# hello328p-v1.net
KiCad netlist of a schematic drawn in EAGLE
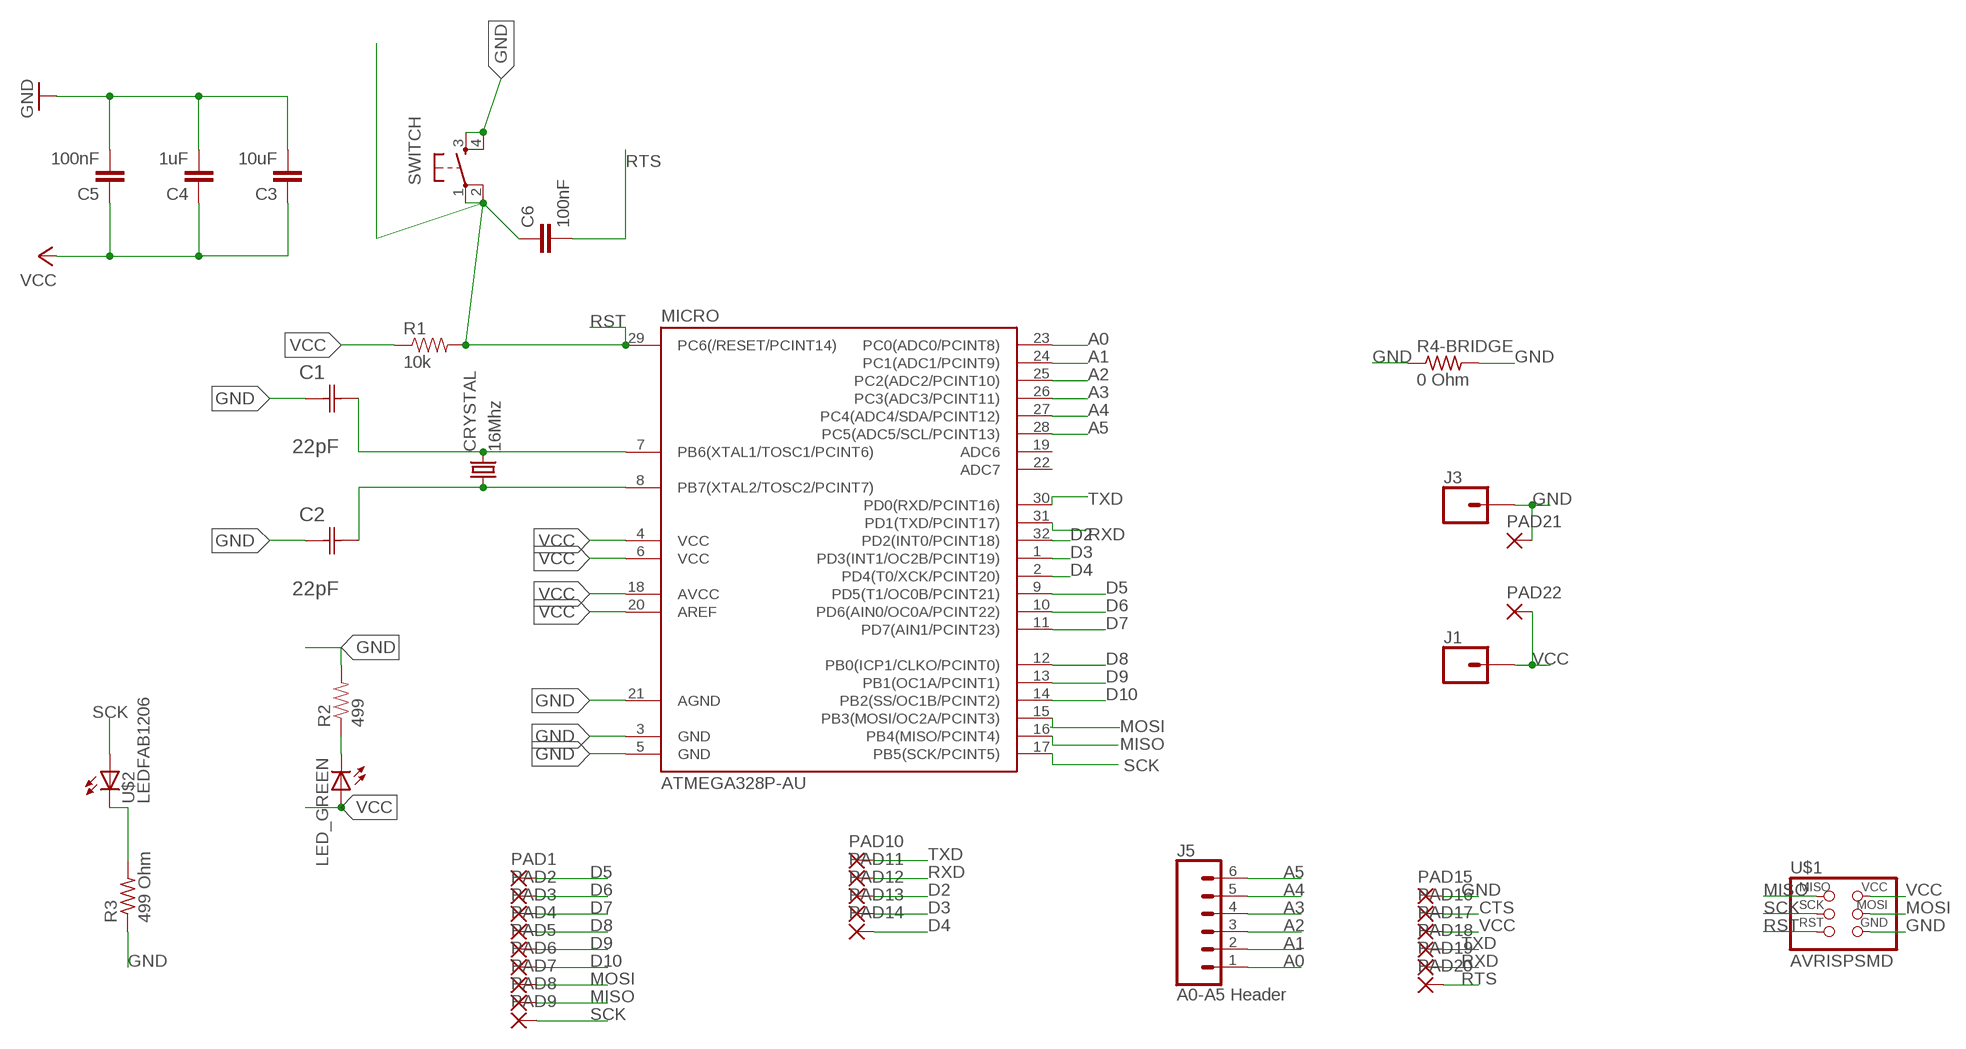
[diagram p0: schematic, sheet 1]

(export (version "E")
  (design (tool "Eeschema 10.0.6"))
  (components
    (comp (ref "C1")
      (value "22pF")
      (footprint "eagle-import:CAPC3216X178N")
      (fields (field (name "MPN") "0612ZC225MAT2A") (field (name "TOLERANCE") "±20%"))
      (libsource (lib "eagle-import") (part "0612ZC225MAT2A"))
    )
    (comp (ref "C2")
      (value "22pF")
      (footprint "eagle-import:CAPC3216X178N")
      (fields (field (name "MPN") "0612ZC225MAT2A") (field (name "TOLERANCE") "±20%"))
      (libsource (lib "eagle-import") (part "0612ZC225MAT2A"))
    )
    (comp (ref "C3")
      (value "10uF")
      (footprint "eagle-import:1206")
      (libsource (lib "eagle-import") (part "CAP1206"))
    )
    (comp (ref "C4")
      (value "1uF")
      (footprint "eagle-import:1206")
      (libsource (lib "eagle-import") (part "CAP1206"))
    )
    (comp (ref "C5")
      (value "100nF")
      (footprint "eagle-import:1206")
      (libsource (lib "eagle-import") (part "CAP1206"))
    )
    (comp (ref "C6")
      (value "100nF")
      (footprint "eagle-import:1206")
      (libsource (lib "eagle-import") (part "CAP1206"))
    )
    (comp (ref "CRYSTAL")
      (value "16Mhz")
      (footprint "eagle-import:CSM-7X-DU")
      (libsource (lib "eagle-import") (part "CSM-7X-DU"))
    )
    (comp (ref "J1")
      (value "CONN_01SNAP-MALE")
      (footprint "eagle-import:SNAP-MALE")
      (libsource (lib "eagle-import") (part "CONN_01SNAP-MALE"))
    )
    (comp (ref "J3")
      (value "CONN_01SNAP-MALE")
      (footprint "eagle-import:SNAP-MALE")
      (libsource (lib "eagle-import") (part "CONN_01SNAP-MALE"))
    )
    (comp (ref "J5")
      (value "A0-A5 Header")
      (footprint "eagle-import:1X06_SMD_MALE")
      (libsource (lib "eagle-import") (part "CONN_06SMD_MALE"))
    )
    (comp (ref "LED_GREEN")
      (value "LED1206")
      (footprint "eagle-import:1206")
      (libsource (lib "eagle-import") (part "LED1206"))
    )
    (comp (ref "MICRO")
      (value "ATMEGA328P-AU")
      (footprint "eagle-import:TQFP32-08")
      (libsource (lib "eagle-import") (part "ATMEGA48/88/168-AU"))
    )
    (comp (ref "PAD1")
      (value "SMD2")
      (footprint "eagle-import:SMD1,27-2,54")
      (libsource (lib "eagle-import") (part "SMD2"))
    )
    (comp (ref "PAD2")
      (value "SMD2")
      (footprint "eagle-import:SMD1,27-2,54")
      (libsource (lib "eagle-import") (part "SMD2"))
    )
    (comp (ref "PAD3")
      (value "SMD2")
      (footprint "eagle-import:SMD1,27-2,54")
      (libsource (lib "eagle-import") (part "SMD2"))
    )
    (comp (ref "PAD4")
      (value "SMD2")
      (footprint "eagle-import:SMD1,27-2,54")
      (libsource (lib "eagle-import") (part "SMD2"))
    )
    (comp (ref "PAD5")
      (value "SMD2")
      (footprint "eagle-import:SMD1,27-2,54")
      (libsource (lib "eagle-import") (part "SMD2"))
    )
    (comp (ref "PAD6")
      (value "SMD2")
      (footprint "eagle-import:SMD1,27-2,54")
      (libsource (lib "eagle-import") (part "SMD2"))
    )
    (comp (ref "PAD7")
      (value "SMD2")
      (footprint "eagle-import:SMD1,27-2,54")
      (libsource (lib "eagle-import") (part "SMD2"))
    )
    (comp (ref "PAD8")
      (value "SMD2")
      (footprint "eagle-import:SMD1,27-2,54")
      (libsource (lib "eagle-import") (part "SMD2"))
    )
    (comp (ref "PAD9")
      (value "SMD2")
      (footprint "eagle-import:SMD1,27-2,54")
      (libsource (lib "eagle-import") (part "SMD2"))
    )
    (comp (ref "PAD10")
      (value "SMD2")
      (footprint "eagle-import:SMD1,27-2,54")
      (libsource (lib "eagle-import") (part "SMD2"))
    )
    (comp (ref "PAD11")
      (value "SMD2")
      (footprint "eagle-import:SMD1,27-2,54")
      (libsource (lib "eagle-import") (part "SMD2"))
    )
    (comp (ref "PAD12")
      (value "SMD2")
      (footprint "eagle-import:SMD1,27-2,54")
      (libsource (lib "eagle-import") (part "SMD2"))
    )
    (comp (ref "PAD13")
      (value "SMD2")
      (footprint "eagle-import:SMD1,27-2,54")
      (libsource (lib "eagle-import") (part "SMD2"))
    )
    (comp (ref "PAD14")
      (value "SMD2")
      (footprint "eagle-import:SMD1,27-2,54")
      (libsource (lib "eagle-import") (part "SMD2"))
    )
    (comp (ref "PAD15")
      (value "SMD2")
      (footprint "eagle-import:SMD1,27-2,54")
      (libsource (lib "eagle-import") (part "SMD2"))
    )
    (comp (ref "PAD16")
      (value "SMD2")
      (footprint "eagle-import:SMD1,27-2,54")
      (libsource (lib "eagle-import") (part "SMD2"))
    )
    (comp (ref "PAD17")
      (value "SMD2")
      (footprint "eagle-import:SMD1,27-2,54")
      (libsource (lib "eagle-import") (part "SMD2"))
    )
    (comp (ref "PAD18")
      (value "SMD2")
      (footprint "eagle-import:SMD1,27-2,54")
      (libsource (lib "eagle-import") (part "SMD2"))
    )
    (comp (ref "PAD19")
      (value "SMD2")
      (footprint "eagle-import:SMD1,27-2,54")
      (libsource (lib "eagle-import") (part "SMD2"))
    )
    (comp (ref "PAD20")
      (value "SMD2")
      (footprint "eagle-import:SMD1,27-2,54")
      (libsource (lib "eagle-import") (part "SMD2"))
    )
    (comp (ref "PAD21")
      (value "SMD2")
      (footprint "eagle-import:SMD1,27-2,54")
      (libsource (lib "eagle-import") (part "SMD2"))
    )
    (comp (ref "PAD22")
      (value "SMD2")
      (footprint "eagle-import:SMD1,27-2,54")
      (libsource (lib "eagle-import") (part "SMD2"))
    )
    (comp (ref "R1")
      (value "10k")
      (footprint "eagle-import:1206")
      (libsource (lib "eagle-import") (part "RESISTOR1206"))
    )
    (comp (ref "R2")
      (value "499")
      (footprint "eagle-import:1206")
      (libsource (lib "eagle-import") (part "RESISTOR1206"))
    )
    (comp (ref "R3")
      (value "499 Ohm")
      (footprint "eagle-import:R1206FAB")
      (libsource (lib "eagle-import") (part "RES-US1206FAB"))
    )
    (comp (ref "R4-BRIDGE")
      (value "0 Ohm")
      (footprint "eagle-import:R1206FAB")
      (libsource (lib "eagle-import") (part "RES-US1206FAB"))
    )
    (comp (ref "SWITCH")
      (value "6MM_SWITCH6MM_SWITCH")
      (footprint "eagle-import:6MM_SWITCH")
      (libsource (lib "eagle-import") (part "6MM_SWITCH6MM_SWITCH"))
    )
    (comp (ref "U$1")
      (value "AVRISPSMD")
      (footprint "eagle-import:2X03SMD")
      (libsource (lib "eagle-import") (part "AVRISPSMD"))
    )
    (comp (ref "U$2")
      (value "LEDFAB1206")
      (footprint "eagle-import:LED1206FAB")
      (libsource (lib "eagle-import") (part "LEDFAB1206"))
    )
  )
  (nets
    (net (code "1") (name "/A0") (class "Default")
      (node (ref "J5") (pin "1") (pinfunction "1_1") (pintype "passive"))
      (node (ref "MICRO") (pin "23") (pinfunction "PC0(ADC0/PCINT8)_23") (pintype "bidirectional"))
    )
    (net (code "2") (name "/A1") (class "Default")
      (node (ref "J5") (pin "2") (pinfunction "2_2") (pintype "passive"))
      (node (ref "MICRO") (pin "24") (pinfunction "PC1(ADC1/PCINT9)_24") (pintype "bidirectional"))
    )
    (net (code "3") (name "/A2") (class "Default")
      (node (ref "J5") (pin "3") (pinfunction "3_3") (pintype "passive"))
      (node (ref "MICRO") (pin "25") (pinfunction "PC2(ADC2/PCINT10)_25") (pintype "bidirectional"))
    )
    (net (code "4") (name "/A3") (class "Default")
      (node (ref "J5") (pin "4") (pinfunction "4_4") (pintype "passive"))
      (node (ref "MICRO") (pin "26") (pinfunction "PC3(ADC3/PCINT11)_26") (pintype "bidirectional"))
    )
    (net (code "5") (name "/A4") (class "Default")
      (node (ref "J5") (pin "5") (pinfunction "5_5") (pintype "passive"))
      (node (ref "MICRO") (pin "27") (pinfunction "PC4(ADC4/SDA/PCINT12)_27") (pintype "bidirectional"))
    )
    (net (code "6") (name "/A5") (class "Default")
      (node (ref "J5") (pin "6") (pinfunction "6_6") (pintype "passive"))
      (node (ref "MICRO") (pin "28") (pinfunction "PC5(ADC5/SCL/PCINT13)_28") (pintype "bidirectional"))
    )
    (net (code "7") (name "/CTS") (class "Default")
      (node (ref "PAD16") (pin "1") (pinfunction "P_1") (pintype "passive"))
    )
    (net (code "8") (name "/D2") (class "Default")
      (node (ref "MICRO") (pin "32") (pinfunction "PD2(INT0/PCINT18)_32") (pintype "bidirectional"))
      (node (ref "PAD12") (pin "1") (pinfunction "P_1") (pintype "passive"))
    )
    (net (code "9") (name "/D3") (class "Default")
      (node (ref "MICRO") (pin "1") (pinfunction "PD3(INT1/OC2B/PCINT19)_1") (pintype "bidirectional"))
      (node (ref "PAD13") (pin "1") (pinfunction "P_1") (pintype "passive"))
    )
    (net (code "10") (name "/D4") (class "Default")
      (node (ref "MICRO") (pin "2") (pinfunction "PD4(T0/XCK/PCINT20)_2") (pintype "bidirectional"))
      (node (ref "PAD14") (pin "1") (pinfunction "P_1") (pintype "passive"))
    )
    (net (code "11") (name "/D5") (class "Default")
      (node (ref "MICRO") (pin "9") (pinfunction "PD5(T1/OC0B/PCINT21)_9") (pintype "bidirectional"))
      (node (ref "PAD1") (pin "1") (pinfunction "P_1") (pintype "passive"))
    )
    (net (code "12") (name "/D6") (class "Default")
      (node (ref "MICRO") (pin "10") (pinfunction "PD6(AIN0/OC0A/PCINT22)_10") (pintype "bidirectional"))
      (node (ref "PAD2") (pin "1") (pinfunction "P_1") (pintype "passive"))
    )
    (net (code "13") (name "/D7") (class "Default")
      (node (ref "MICRO") (pin "11") (pinfunction "PD7(AIN1/PCINT23)_11") (pintype "bidirectional"))
      (node (ref "PAD3") (pin "1") (pinfunction "P_1") (pintype "passive"))
    )
    (net (code "14") (name "/D8") (class "Default")
      (node (ref "MICRO") (pin "12") (pinfunction "PB0(ICP1/CLKO/PCINT0)_12") (pintype "bidirectional"))
      (node (ref "PAD4") (pin "1") (pinfunction "P_1") (pintype "passive"))
    )
    (net (code "15") (name "/D9") (class "Default")
      (node (ref "MICRO") (pin "13") (pinfunction "PB1(OC1A/PCINT1)_13") (pintype "bidirectional"))
      (node (ref "PAD5") (pin "1") (pinfunction "P_1") (pintype "passive"))
    )
    (net (code "16") (name "/D10") (class "Default")
      (node (ref "MICRO") (pin "14") (pinfunction "PB2(SS/OC1B/PCINT2)_14") (pintype "bidirectional"))
      (node (ref "PAD6") (pin "1") (pinfunction "P_1") (pintype "passive"))
    )
    (net (code "17") (name "/MISO") (class "Default")
      (node (ref "MICRO") (pin "16") (pinfunction "PB4(MISO/PCINT4)_16") (pintype "bidirectional"))
      (node (ref "PAD8") (pin "1") (pinfunction "P_1") (pintype "passive"))
      (node (ref "U$1") (pin "1") (pinfunction "MISO_1") (pintype "passive"))
    )
    (net (code "18") (name "/MOSI") (class "Default")
      (node (ref "MICRO") (pin "15") (pinfunction "PB3(MOSI/OC2A/PCINT3)_15") (pintype "bidirectional"))
      (node (ref "PAD7") (pin "1") (pinfunction "P_1") (pintype "passive"))
      (node (ref "U$1") (pin "4") (pinfunction "MOSI_4") (pintype "passive"))
    )
    (net (code "19") (name "/RST") (class "Default")
      (node (ref "C6") (pin "1") (pinfunction "1_1") (pintype "passive"))
      (node (ref "MICRO") (pin "29") (pinfunction "PC6(/RESET/PCINT14)_29") (pintype "bidirectional"))
      (node (ref "R1") (pin "2") (pinfunction "2_2") (pintype "passive"))
      (node (ref "SWITCH") (pin "1") (pinfunction "P_1") (pintype "passive"))
      (node (ref "SWITCH") (pin "2") (pinfunction "P1_2") (pintype "passive"))
      (node (ref "U$1") (pin "5") (pinfunction "RST_5") (pintype "passive"))
    )
    (net (code "20") (name "/RTS") (class "Default")
      (node (ref "C6") (pin "2") (pinfunction "2_2") (pintype "passive"))
      (node (ref "PAD20") (pin "1") (pinfunction "P_1") (pintype "passive"))
    )
    (net (code "21") (name "/RXD") (class "Default")
      (node (ref "MICRO") (pin "31") (pinfunction "PD1(TXD/PCINT17)_31") (pintype "bidirectional"))
      (node (ref "PAD11") (pin "1") (pinfunction "P_1") (pintype "passive"))
      (node (ref "PAD19") (pin "1") (pinfunction "P_1") (pintype "passive"))
    )
    (net (code "22") (name "/SCK") (class "Default")
      (node (ref "MICRO") (pin "17") (pinfunction "PB5(SCK/PCINT5)_17") (pintype "bidirectional"))
      (node (ref "PAD9") (pin "1") (pinfunction "P_1") (pintype "passive"))
      (node (ref "U$1") (pin "3") (pinfunction "SCK_3") (pintype "passive"))
      (node (ref "U$2") (pin "1") (pinfunction "A_1") (pintype "passive"))
    )
    (net (code "23") (name "/TXD") (class "Default")
      (node (ref "MICRO") (pin "30") (pinfunction "PD0(RXD/PCINT16)_30") (pintype "bidirectional"))
      (node (ref "PAD10") (pin "1") (pinfunction "P_1") (pintype "passive"))
      (node (ref "PAD18") (pin "1") (pinfunction "P_1") (pintype "passive"))
    )
    (net (code "24") (name "GND") (class "Default")
      (node (ref "C1") (pin "1") (pinfunction "C1_1") (pintype "passive"))
      (node (ref "C2") (pin "1") (pinfunction "C1_1") (pintype "passive"))
      (node (ref "C3") (pin "2") (pinfunction "2_2") (pintype "passive"))
      (node (ref "C4") (pin "2") (pinfunction "2_2") (pintype "passive"))
      (node (ref "C5") (pin "2") (pinfunction "2_2") (pintype "passive"))
      (node (ref "J3") (pin "2") (pinfunction "1_2") (pintype "passive"))
      (node (ref "MICRO") (pin "21") (pinfunction "AGND_21") (pintype "power_in"))
      (node (ref "MICRO") (pin "3") (pinfunction "GND_3") (pintype "power_in"))
      (node (ref "MICRO") (pin "5") (pinfunction "GND_5") (pintype "power_in"))
      (node (ref "PAD15") (pin "1") (pinfunction "P_1") (pintype "passive"))
      (node (ref "PAD21") (pin "1") (pinfunction "P_1") (pintype "passive"))
      (node (ref "R2") (pin "2") (pinfunction "2_2") (pintype "passive"))
      (node (ref "R3") (pin "1") (pinfunction "1_1") (pintype "passive"))
      (node (ref "R4-BRIDGE") (pin "1") (pinfunction "1_1") (pintype "passive"))
      (node (ref "R4-BRIDGE") (pin "2") (pinfunction "2_2") (pintype "passive"))
      (node (ref "SWITCH") (pin "3") (pinfunction "S_3") (pintype "passive"))
      (node (ref "SWITCH") (pin "4") (pinfunction "S1_4") (pintype "passive"))
      (node (ref "U$1") (pin "6") (pinfunction "GND_6") (pintype "passive"))
    )
    (net (code "25") (name "Net-(C1-C2)") (class "Default")
      (node (ref "C1") (pin "2") (pinfunction "C2_2") (pintype "passive"))
      (node (ref "CRYSTAL") (pin "2") (pinfunction "2_2") (pintype "passive"))
      (node (ref "MICRO") (pin "7") (pinfunction "PB6(XTAL1/TOSC1/PCINT6)_7") (pintype "bidirectional"))
    )
    (net (code "26") (name "Net-(C2-C2)") (class "Default")
      (node (ref "C2") (pin "2") (pinfunction "C2_2") (pintype "passive"))
      (node (ref "CRYSTAL") (pin "1") (pinfunction "1_1") (pintype "passive"))
      (node (ref "MICRO") (pin "8") (pinfunction "PB7(XTAL2/TOSC2/PCINT7)_8") (pintype "bidirectional"))
    )
    (net (code "27") (name "Net-(LED_GREEN-C)") (class "Default")
      (node (ref "LED_GREEN") (pin "2") (pinfunction "C_2") (pintype "passive"))
      (node (ref "R2") (pin "1") (pinfunction "1_1") (pintype "passive"))
    )
    (net (code "28") (name "Net-(U$2-C)") (class "Default")
      (node (ref "R3") (pin "2") (pinfunction "2_2") (pintype "passive"))
      (node (ref "U$2") (pin "2") (pinfunction "C_2") (pintype "passive"))
    )
    (net (code "29") (name "VCC") (class "Default")
      (node (ref "C3") (pin "1") (pinfunction "1_1") (pintype "passive"))
      (node (ref "C4") (pin "1") (pinfunction "1_1") (pintype "passive"))
      (node (ref "C5") (pin "1") (pinfunction "1_1") (pintype "passive"))
      (node (ref "J1") (pin "2") (pinfunction "1_2") (pintype "passive"))
      (node (ref "LED_GREEN") (pin "1") (pinfunction "A_1") (pintype "passive"))
      (node (ref "MICRO") (pin "18") (pinfunction "AVCC_18") (pintype "passive"))
      (node (ref "MICRO") (pin "20") (pinfunction "AREF_20") (pintype "passive"))
      (node (ref "MICRO") (pin "4") (pinfunction "VCC_4") (pintype "power_in"))
      (node (ref "MICRO") (pin "6") (pinfunction "VCC_6") (pintype "power_in"))
      (node (ref "PAD17") (pin "1") (pinfunction "P_1") (pintype "passive"))
      (node (ref "PAD22") (pin "1") (pinfunction "P_1") (pintype "passive"))
      (node (ref "R1") (pin "1") (pinfunction "1_1") (pintype "passive"))
      (node (ref "U$1") (pin "2") (pinfunction "VCC_2") (pintype "passive"))
    )
    (net (code "30") (name "unconnected-(MICRO-ADC6-Pad19)") (class "Default")
      (node (ref "MICRO") (pin "19") (pinfunction "ADC6_19") (pintype "passive"))
    )
    (net (code "31") (name "unconnected-(MICRO-ADC7-Pad22)") (class "Default")
      (node (ref "MICRO") (pin "22") (pinfunction "ADC7_22") (pintype "passive"))
    )
  )
)
